# Remote_Control_v1.net
KiCad netlist of a schematic drawn in EAGLE
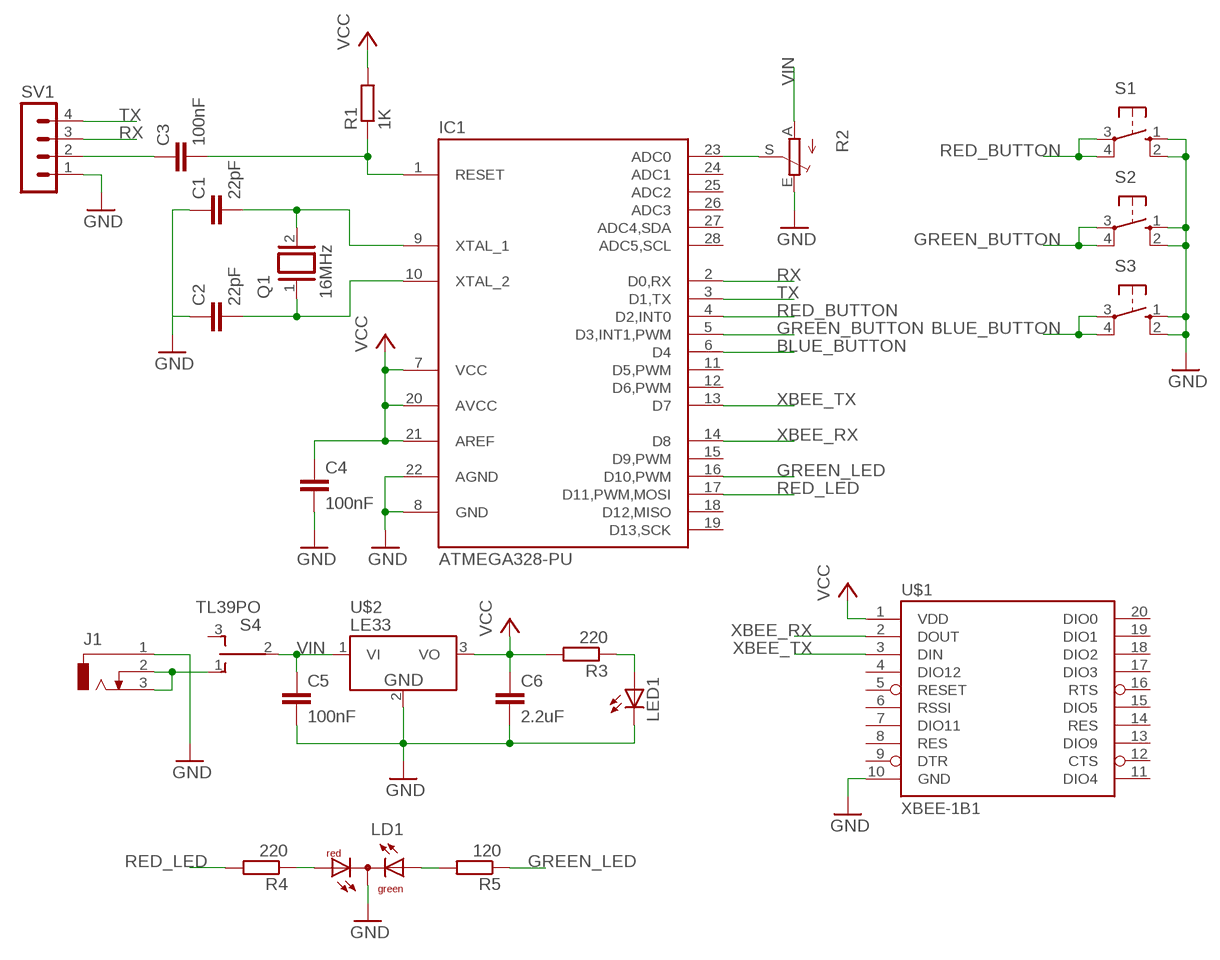
[diagram p0: schematic, sheet 1]

(export (version "E")
  (design (tool "Eeschema 10.0.6"))
  (components
    (comp (ref "C1")
      (value "22pF")
      (footprint "eagle-import:C050-024X044")
      (libsource (lib "eagle-import") (part "C-EU050-024X044"))
    )
    (comp (ref "C2")
      (value "22pF")
      (footprint "eagle-import:C050-024X044")
      (libsource (lib "eagle-import") (part "C-EU050-024X044"))
    )
    (comp (ref "C3")
      (value "100nF")
      (footprint "eagle-import:C050-025X075")
      (libsource (lib "eagle-import") (part "C-EU050-025X075"))
    )
    (comp (ref "C4")
      (value "100nF")
      (footprint "eagle-import:C050-025X075")
      (libsource (lib "eagle-import") (part "C-EU050-025X075"))
    )
    (comp (ref "C5")
      (value "100nF")
      (footprint "eagle-import:C050-025X075")
      (libsource (lib "eagle-import") (part "C-EU050-025X075"))
    )
    (comp (ref "C6")
      (value "2.2uF")
      (footprint "eagle-import:C050-035X075")
      (libsource (lib "eagle-import") (part "C-EU050-035X075"))
    )
    (comp (ref "IC1")
      (value "ATMEGA328-PU")
      (footprint "eagle-import:DIL28-3")
      (libsource (lib "eagle-import") (part "ATMEGA328-PU"))
    )
    (comp (ref "J1")
      (value "DCJ0303")
      (footprint "eagle-import:DCJ0303")
      (libsource (lib "eagle-import") (part "DCJ0303"))
    )
    (comp (ref "LD1")
      (value "DUOLED-RG-C")
      (footprint "eagle-import:DUOLED-C-5MM")
      (libsource (lib "eagle-import") (part "DUOLED-RG-C"))
    )
    (comp (ref "LED1")
      (value "LED3MM")
      (footprint "eagle-import:LED3MM")
      (libsource (lib "eagle-import") (part "LED3MM"))
    )
    (comp (ref "Q1")
      (value "16MHz")
      (footprint "eagle-import:QS")
      (libsource (lib "eagle-import") (part "XTAL/S"))
    )
    (comp (ref "R1")
      (value "1K")
      (footprint "eagle-import:0207_7")
      (libsource (lib "eagle-import") (part "R-EU_0207/7"))
    )
    (comp (ref "R2")
      (value "TRIM_EU-CA9V")
      (footprint "eagle-import:CA9V")
      (libsource (lib "eagle-import") (part "TRIM_EU-CA9V"))
    )
    (comp (ref "R3")
      (value "220")
      (footprint "eagle-import:0207_7")
      (libsource (lib "eagle-import") (part "R-EU_0207/7"))
    )
    (comp (ref "R4")
      (value "220")
      (footprint "eagle-import:0207_7")
      (libsource (lib "eagle-import") (part "R-EU_0207/7"))
    )
    (comp (ref "R5")
      (value "120")
      (footprint "eagle-import:0207_7")
      (libsource (lib "eagle-import") (part "R-EU_0207/7"))
    )
    (comp (ref "S1")
      (value "40-XX")
      (footprint "eagle-import:B3F-40XX")
      (fields (field (name "MF") "OMRON COMPONENTS USA") (field (name "MPN") "B3F-4000"))
      (libsource (lib "eagle-import") (part "40-XX"))
    )
    (comp (ref "S2")
      (value "40-XX")
      (footprint "eagle-import:B3F-40XX")
      (fields (field (name "MF") "OMRON COMPONENTS USA") (field (name "MPN") "B3F-4000"))
      (libsource (lib "eagle-import") (part "40-XX"))
    )
    (comp (ref "S3")
      (value "40-XX")
      (footprint "eagle-import:B3F-40XX")
      (fields (field (name "MF") "OMRON COMPONENTS USA") (field (name "MPN") "B3F-4000"))
      (libsource (lib "eagle-import") (part "40-XX"))
    )
    (comp (ref "S4")
      (value "TL39PO")
      (footprint "eagle-import:TL3XPO")
      (libsource (lib "eagle-import") (part "TL39PO"))
    )
    (comp (ref "SV1")
      (value "MA04-1")
      (footprint "eagle-import:MA04-1")
      (libsource (lib "eagle-import") (part "MA04-1"))
    )
    (comp (ref "U$1")
      (value "XBEE-1B1")
      (footprint "eagle-import:XBEE-1")
      (libsource (lib "eagle-import") (part "XBEE-1B1"))
    )
    (comp (ref "U$2")
      (value "LE33")
      (footprint "eagle-import:TO-92")
      (libsource (lib "eagle-import") (part "LE33"))
    )
  )
  (nets
    (net (code "1") (name "/BLUE_BUTTON") (class "Default")
      (node (ref "IC1") (pin "6") (pinfunction "D4_6") (pintype "bidirectional"))
      (node (ref "S3") (pin "3") (pinfunction "P_3") (pintype "passive"))
      (node (ref "S3") (pin "4") (pinfunction "P1_4") (pintype "passive"))
    )
    (net (code "2") (name "/GREEN_BUTTON") (class "Default")
      (node (ref "IC1") (pin "5") (pinfunction "D3,INT1,PWM_5") (pintype "bidirectional"))
      (node (ref "S2") (pin "3") (pinfunction "P_3") (pintype "passive"))
      (node (ref "S2") (pin "4") (pinfunction "P1_4") (pintype "passive"))
    )
    (net (code "3") (name "/GREEN_LED") (class "Default")
      (node (ref "IC1") (pin "16") (pinfunction "D10,PWM_16") (pintype "bidirectional"))
      (node (ref "R5") (pin "1") (pinfunction "1_1") (pintype "passive"))
    )
    (net (code "4") (name "/RED_BUTTON") (class "Default")
      (node (ref "IC1") (pin "4") (pinfunction "D2,INT0_4") (pintype "bidirectional"))
      (node (ref "S1") (pin "3") (pinfunction "P_3") (pintype "passive"))
      (node (ref "S1") (pin "4") (pinfunction "P1_4") (pintype "passive"))
    )
    (net (code "5") (name "/RED_LED") (class "Default")
      (node (ref "IC1") (pin "17") (pinfunction "D11,PWM,MOSI_17") (pintype "bidirectional"))
      (node (ref "R4") (pin "2") (pinfunction "2_2") (pintype "passive"))
    )
    (net (code "6") (name "/RX") (class "Default")
      (node (ref "IC1") (pin "2") (pinfunction "D0,RX_2") (pintype "bidirectional"))
      (node (ref "SV1") (pin "3") (pinfunction "3_3") (pintype "passive"))
    )
    (net (code "7") (name "/TX") (class "Default")
      (node (ref "IC1") (pin "3") (pinfunction "D1,TX_3") (pintype "bidirectional"))
      (node (ref "SV1") (pin "4") (pinfunction "4_4") (pintype "passive"))
    )
    (net (code "8") (name "/VIN") (class "Default")
      (node (ref "C5") (pin "1") (pinfunction "1_1") (pintype "passive"))
      (node (ref "R2") (pin "A") (pinfunction "A_A") (pintype "passive"))
      (node (ref "S4") (pin "2") (pinfunction "P_2") (pintype "passive"))
      (node (ref "U$2") (pin "1") (pinfunction "VI_1") (pintype "bidirectional"))
    )
    (net (code "9") (name "/XBEE_RX") (class "Default")
      (node (ref "IC1") (pin "14") (pinfunction "D8_14") (pintype "bidirectional"))
      (node (ref "U$1") (pin "2") (pinfunction "DOUT_2") (pintype "output"))
    )
    (net (code "10") (name "/XBEE_TX") (class "Default")
      (node (ref "IC1") (pin "13") (pinfunction "D7_13") (pintype "bidirectional"))
      (node (ref "U$1") (pin "3") (pinfunction "DIN_3") (pintype "input"))
    )
    (net (code "11") (name "GND") (class "Default")
      (node (ref "C1") (pin "1") (pinfunction "1_1") (pintype "passive"))
      (node (ref "C2") (pin "1") (pinfunction "1_1") (pintype "passive"))
      (node (ref "C4") (pin "2") (pinfunction "2_2") (pintype "passive"))
      (node (ref "C5") (pin "2") (pinfunction "2_2") (pintype "passive"))
      (node (ref "C6") (pin "2") (pinfunction "2_2") (pintype "passive"))
      (node (ref "IC1") (pin "22") (pinfunction "AGND_22") (pintype "power_in"))
      (node (ref "IC1") (pin "8") (pinfunction "GND_8") (pintype "power_in"))
      (node (ref "J1") (pin "1") (pinfunction "1_1") (pintype "passive"))
      (node (ref "LD1") (pin "C") (pinfunction "C_C") (pintype "passive"))
      (node (ref "LED1") (pin "K") (pinfunction "C_K") (pintype "passive"))
      (node (ref "R2") (pin "E") (pinfunction "E_E") (pintype "passive"))
      (node (ref "S1") (pin "1") (pinfunction "S_1") (pintype "passive"))
      (node (ref "S1") (pin "2") (pinfunction "S1_2") (pintype "passive"))
      (node (ref "S2") (pin "1") (pinfunction "S_1") (pintype "passive"))
      (node (ref "S2") (pin "2") (pinfunction "S1_2") (pintype "passive"))
      (node (ref "S3") (pin "1") (pinfunction "S_1") (pintype "passive"))
      (node (ref "S3") (pin "2") (pinfunction "S1_2") (pintype "passive"))
      (node (ref "SV1") (pin "1") (pinfunction "1_1") (pintype "passive"))
      (node (ref "U$1") (pin "10") (pinfunction "GND_10") (pintype "power_in"))
      (node (ref "U$2") (pin "2") (pinfunction "GND_2") (pintype "bidirectional"))
    )
    (net (code "12") (name "Net-(C3-Pad1)") (class "Default")
      (node (ref "C3") (pin "1") (pinfunction "1_1") (pintype "passive"))
      (node (ref "SV1") (pin "2") (pinfunction "2_2") (pintype "passive"))
    )
    (net (code "13") (name "Net-(IC1-ADC0)") (class "Default")
      (node (ref "IC1") (pin "23") (pinfunction "ADC0_23") (pintype "bidirectional"))
      (node (ref "R2") (pin "S") (pinfunction "S_S") (pintype "passive"))
    )
    (net (code "14") (name "Net-(IC1-RESET)") (class "Default")
      (node (ref "C3") (pin "2") (pinfunction "2_2") (pintype "passive"))
      (node (ref "IC1") (pin "1") (pinfunction "RESET_1") (pintype "bidirectional"))
      (node (ref "R1") (pin "1") (pinfunction "1_1") (pintype "passive"))
    )
    (net (code "15") (name "Net-(IC1-XTAL_1)") (class "Default")
      (node (ref "C1") (pin "2") (pinfunction "2_2") (pintype "passive"))
      (node (ref "IC1") (pin "9") (pinfunction "XTAL_1_9") (pintype "bidirectional"))
      (node (ref "Q1") (pin "2") (pinfunction "2_2") (pintype "passive"))
    )
    (net (code "16") (name "Net-(IC1-XTAL_2)") (class "Default")
      (node (ref "C2") (pin "2") (pinfunction "2_2") (pintype "passive"))
      (node (ref "IC1") (pin "10") (pinfunction "XTAL_2_10") (pintype "bidirectional"))
      (node (ref "Q1") (pin "1") (pinfunction "1_1") (pintype "passive"))
    )
    (net (code "17") (name "Net-(LD1-AG)") (class "Default")
      (node (ref "LD1") (pin "AX") (pinfunction "AG_AX") (pintype "passive"))
      (node (ref "R5") (pin "2") (pinfunction "2_2") (pintype "passive"))
    )
    (net (code "18") (name "Net-(LD1-PadAR)") (class "Default")
      (node (ref "LD1") (pin "AR") (pinfunction "AR_AR") (pintype "passive"))
      (node (ref "R4") (pin "1") (pinfunction "1_1") (pintype "passive"))
    )
    (net (code "19") (name "Net-(LED1-PadA)") (class "Default")
      (node (ref "LED1") (pin "A") (pinfunction "A_A") (pintype "passive"))
      (node (ref "R3") (pin "1") (pinfunction "1_1") (pintype "passive"))
    )
    (net (code "20") (name "Net-(S4-O)") (class "Default")
      (node (ref "J1") (pin "2") (pinfunction "2_2") (pintype "passive"))
      (node (ref "J1") (pin "3") (pinfunction "3_3") (pintype "passive"))
      (node (ref "S4") (pin "1") (pinfunction "O_1") (pintype "passive"))
    )
    (net (code "21") (name "VCC") (class "Default")
      (node (ref "C4") (pin "1") (pinfunction "1_1") (pintype "passive"))
      (node (ref "C6") (pin "1") (pinfunction "1_1") (pintype "passive"))
      (node (ref "IC1") (pin "20") (pinfunction "AVCC_20") (pintype "passive"))
      (node (ref "IC1") (pin "21") (pinfunction "AREF_21") (pintype "passive"))
      (node (ref "IC1") (pin "7") (pinfunction "VCC_7") (pintype "power_in"))
      (node (ref "R1") (pin "2") (pinfunction "2_2") (pintype "passive"))
      (node (ref "R3") (pin "2") (pinfunction "2_2") (pintype "passive"))
      (node (ref "U$1") (pin "1") (pinfunction "VDD_1") (pintype "power_in"))
      (node (ref "U$2") (pin "3") (pinfunction "VO_3") (pintype "bidirectional"))
    )
    (net (code "22") (name "unconnected-(IC1-ADC1-Pad24)") (class "Default")
      (node (ref "IC1") (pin "24") (pinfunction "ADC1_24") (pintype "bidirectional"))
    )
    (net (code "23") (name "unconnected-(IC1-ADC2-Pad25)") (class "Default")
      (node (ref "IC1") (pin "25") (pinfunction "ADC2_25") (pintype "bidirectional"))
    )
    (net (code "24") (name "unconnected-(IC1-ADC3-Pad26)") (class "Default")
      (node (ref "IC1") (pin "26") (pinfunction "ADC3_26") (pintype "bidirectional"))
    )
    (net (code "25") (name "unconnected-(IC1-ADC4,SDA-Pad27)") (class "Default")
      (node (ref "IC1") (pin "27") (pinfunction "ADC4,SDA_27") (pintype "bidirectional"))
    )
    (net (code "26") (name "unconnected-(IC1-ADC5,SCL-Pad28)") (class "Default")
      (node (ref "IC1") (pin "28") (pinfunction "ADC5,SCL_28") (pintype "bidirectional"))
    )
    (net (code "27") (name "unconnected-(IC1-D5,PWM-Pad11)") (class "Default")
      (node (ref "IC1") (pin "11") (pinfunction "D5,PWM_11") (pintype "bidirectional"))
    )
    (net (code "28") (name "unconnected-(IC1-D6,PWM-Pad12)") (class "Default")
      (node (ref "IC1") (pin "12") (pinfunction "D6,PWM_12") (pintype "bidirectional"))
    )
    (net (code "29") (name "unconnected-(IC1-D9,PWM-Pad15)") (class "Default")
      (node (ref "IC1") (pin "15") (pinfunction "D9,PWM_15") (pintype "bidirectional"))
    )
    (net (code "30") (name "unconnected-(IC1-D12,MISO-Pad18)") (class "Default")
      (node (ref "IC1") (pin "18") (pinfunction "D12,MISO_18") (pintype "bidirectional"))
    )
    (net (code "31") (name "unconnected-(IC1-D13,SCK-Pad19)") (class "Default")
      (node (ref "IC1") (pin "19") (pinfunction "D13,SCK_19") (pintype "bidirectional"))
    )
    (net (code "32") (name "unconnected-(S4-S-Pad3)") (class "Default")
      (node (ref "S4") (pin "3") (pinfunction "S_3") (pintype "passive"))
    )
    (net (code "33") (name "unconnected-(U$1-CTS-Pad12)") (class "Default")
      (node (ref "U$1") (pin "12") (pinfunction "CTS_12") (pintype "output"))
    )
    (net (code "34") (name "unconnected-(U$1-DIO0-Pad20)") (class "Default")
      (node (ref "U$1") (pin "20") (pinfunction "DIO0_20") (pintype "bidirectional"))
    )
    (net (code "35") (name "unconnected-(U$1-DIO1-Pad19)") (class "Default")
      (node (ref "U$1") (pin "19") (pinfunction "DIO1_19") (pintype "bidirectional"))
    )
    (net (code "36") (name "unconnected-(U$1-DIO2-Pad18)") (class "Default")
      (node (ref "U$1") (pin "18") (pinfunction "DIO2_18") (pintype "bidirectional"))
    )
    (net (code "37") (name "unconnected-(U$1-DIO3-Pad17)") (class "Default")
      (node (ref "U$1") (pin "17") (pinfunction "DIO3_17") (pintype "bidirectional"))
    )
    (net (code "38") (name "unconnected-(U$1-DIO4-Pad11)") (class "Default")
      (node (ref "U$1") (pin "11") (pinfunction "DIO4_11") (pintype "bidirectional"))
    )
    (net (code "39") (name "unconnected-(U$1-DIO5-Pad15)") (class "Default")
      (node (ref "U$1") (pin "15") (pinfunction "DIO5_15") (pintype "bidirectional"))
    )
    (net (code "40") (name "unconnected-(U$1-DIO9-Pad13)") (class "Default")
      (node (ref "U$1") (pin "13") (pinfunction "DIO9_13") (pintype "bidirectional"))
    )
    (net (code "41") (name "unconnected-(U$1-DIO11-Pad7)") (class "Default")
      (node (ref "U$1") (pin "7") (pinfunction "DIO11_7") (pintype "bidirectional"))
    )
    (net (code "42") (name "unconnected-(U$1-DIO12-Pad4)") (class "Default")
      (node (ref "U$1") (pin "4") (pinfunction "DIO12_4") (pintype "bidirectional"))
    )
    (net (code "43") (name "unconnected-(U$1-DTR-Pad9)") (class "Default")
      (node (ref "U$1") (pin "9") (pinfunction "DTR_9") (pintype "bidirectional"))
    )
    (net (code "44") (name "unconnected-(U$1-RES-Pad8)") (class "Default")
      (node (ref "U$1") (pin "8") (pinfunction "RES_8") (pintype "bidirectional"))
    )
    (net (code "45") (name "unconnected-(U$1-RES-Pad14)") (class "Default")
      (node (ref "U$1") (pin "14") (pinfunction "RES_14") (pintype "bidirectional"))
    )
    (net (code "46") (name "unconnected-(U$1-RESET-Pad5)") (class "Default")
      (node (ref "U$1") (pin "5") (pinfunction "RESET_5") (pintype "input"))
    )
    (net (code "47") (name "unconnected-(U$1-RSSI-Pad6)") (class "Default")
      (node (ref "U$1") (pin "6") (pinfunction "RSSI_6") (pintype "bidirectional"))
    )
    (net (code "48") (name "unconnected-(U$1-RTS-Pad16)") (class "Default")
      (node (ref "U$1") (pin "16") (pinfunction "RTS_16") (pintype "input"))
    )
  )
)
